# Copy_of_SCH_Placa_presentation.net
KiCad netlist of a schematic drawn in Altium Designer
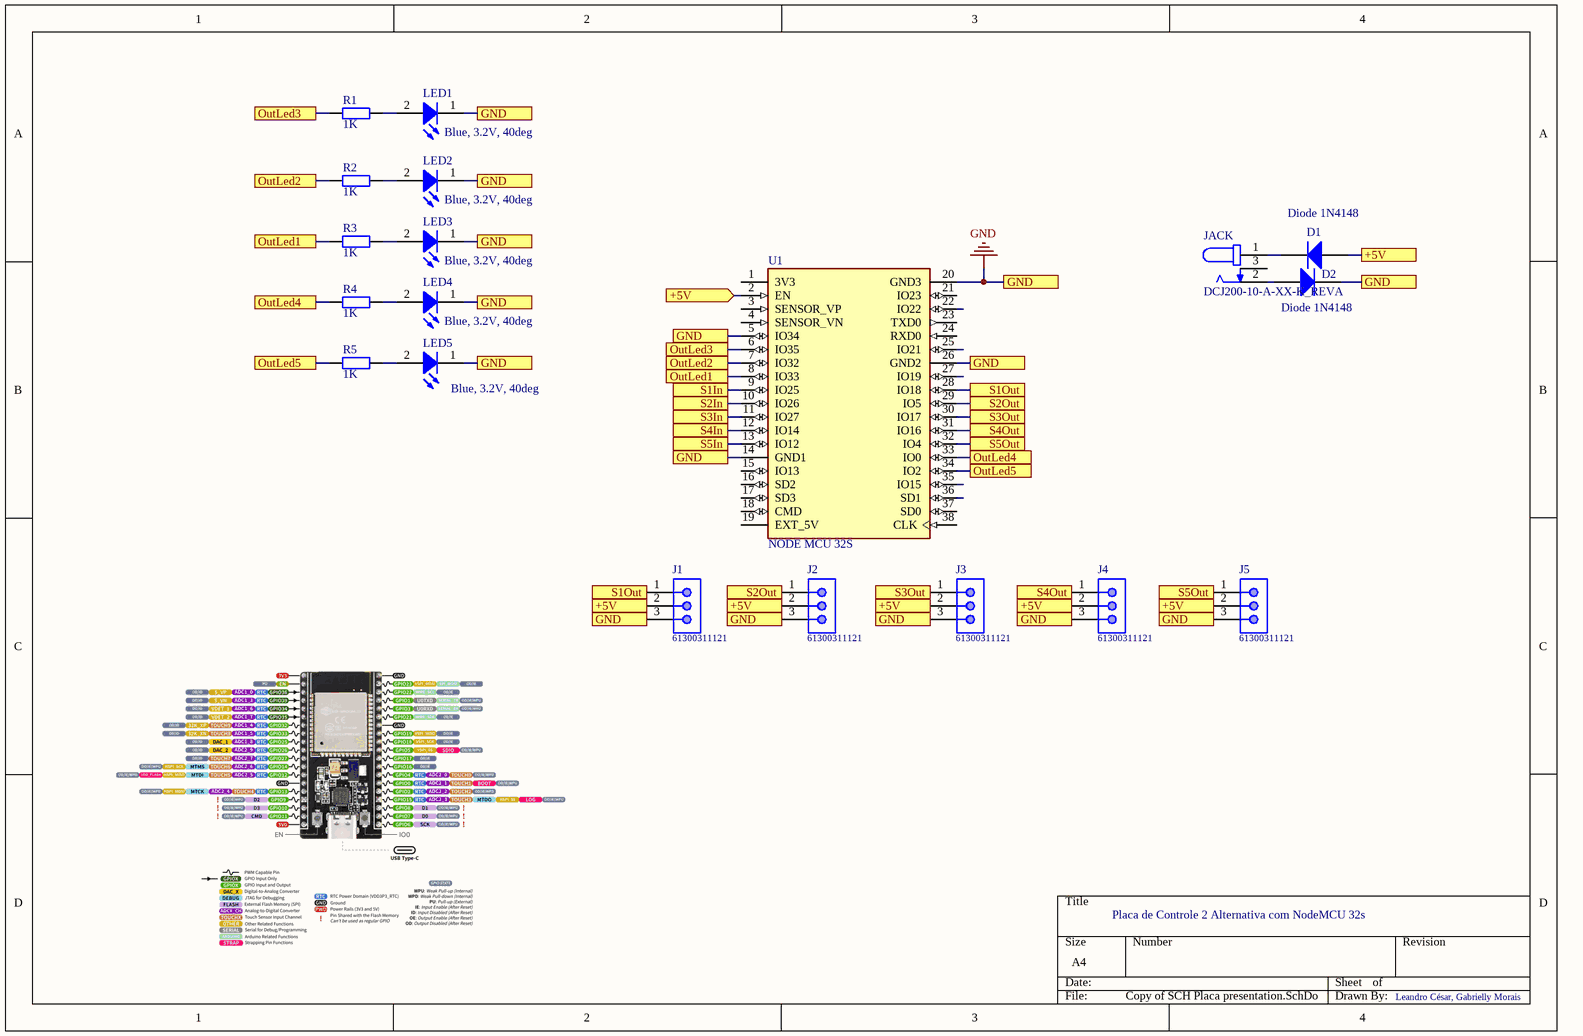
[diagram p0: Copy of SCH Placa presentation.SchDoc]

(export (version "E")
  (design (tool "Eeschema 10.0.6"))
  (components
    (comp (ref "D1")
      (value "Diode 1N4148")
      (footprint "DO-35")
      (description "High Conductance Fast Diode")
      (fields (field (name "PUBLISHER") "Altium Limited"))
      (libsource (lib "Biblioteca_Ex_Machina_v1.6.0") (part "Diode 1N4148"))
    )
    (comp (ref "D2")
      (value "Diode 1N4148")
      (footprint "DO-35")
      (description "High Conductance Fast Diode")
      (fields (field (name "PUBLISHER") "Altium Limited"))
      (libsource (lib "Biblioteca_Ex_Machina_v1.6.0") (part "Diode 1N4148"))
    )
    (comp (ref "J1")
      (value "61300311121")
      (footprint "61300311121")
      (description "WR-PHD Pin Header, THT, pitch 2.54mm, Single Row, Vertical, 3pin")
      (fields (field (name "PUBLISHER") "Wurth Elektronik"))
      (libsource (lib "Biblioteca_Ex_Machina_v1.6.0") (part "61300311121"))
    )
    (comp (ref "J2")
      (value "61300311121")
      (footprint "61300311121")
      (description "WR-PHD Pin Header, THT, pitch 2.54mm, Single Row, Vertical, 3pin")
      (fields (field (name "PUBLISHER") "Wurth Elektronik"))
      (libsource (lib "Biblioteca_Ex_Machina_v1.6.0") (part "61300311121"))
    )
    (comp (ref "J3")
      (value "61300311121")
      (footprint "61300311121")
      (description "WR-PHD Pin Header, THT, pitch 2.54mm, Single Row, Vertical, 3pin")
      (fields (field (name "PUBLISHER") "Wurth Elektronik"))
      (libsource (lib "Biblioteca_Ex_Machina_v1.6.0") (part "61300311121"))
    )
    (comp (ref "J4")
      (value "61300311121")
      (footprint "61300311121")
      (description "WR-PHD Pin Header, THT, pitch 2.54mm, Single Row, Vertical, 3pin")
      (fields (field (name "PUBLISHER") "Wurth Elektronik"))
      (libsource (lib "Biblioteca_Ex_Machina_v1.6.0") (part "61300311121"))
    )
    (comp (ref "J5")
      (value "61300311121")
      (footprint "61300311121")
      (description "WR-PHD Pin Header, THT, pitch 2.54mm, Single Row, Vertical, 3pin")
      (fields (field (name "PUBLISHER") "Wurth Elektronik"))
      (libsource (lib "Biblioteca_Ex_Machina_v1.6.0") (part "61300311121"))
    )
    (comp (ref "JACK")
      (value "DCJ200-10-A-XX-K_REVA")
      (footprint "GCT_DCJ200-10-A-XX-K_REVA")
      (description "Power Barrel Connector Jack 2.05mm ID (0.081), 5.50mm OD (0.217) Through Hole, Right Angle")
      (fields (field (name "MF") "Global Connector Technology") (field (name "MP") "DCJ200-10-A-K1-K"))
      (libsource (lib "DCJ200-10-A-XX-K_REVA (2)") (part "DCJ200-10-A-XX-K_REVA"))
    )
    (comp (ref "LED1")
      (value "Blue, 3.2V, 40deg")
      (footprint "LED RED 3MM")
      (description "LED WL-TMRC THT Mono-color Round")
      (fields (field (name "PART NUMBER") "151051BS04000") (field (name "PUBLISHER") "Wurth Elektronik"))
      (libsource (lib "Biblioteca_Ex_Machina_v1.6.0") (part "LED"))
    )
    (comp (ref "LED2")
      (value "Blue, 3.2V, 40deg")
      (footprint "LED RED 3MM")
      (description "LED WL-TMRC THT Mono-color Round")
      (fields (field (name "PART NUMBER") "151051BS04000") (field (name "PUBLISHER") "Wurth Elektronik"))
      (libsource (lib "Biblioteca_Ex_Machina_v1.6.0") (part "LED"))
    )
    (comp (ref "LED3")
      (value "Blue, 3.2V, 40deg")
      (footprint "LED RED 3MM")
      (description "LED WL-TMRC THT Mono-color Round")
      (fields (field (name "PART NUMBER") "151051BS04000") (field (name "PUBLISHER") "Wurth Elektronik"))
      (libsource (lib "Biblioteca_Ex_Machina_v1.6.0") (part "LED"))
    )
    (comp (ref "LED4")
      (value "Blue, 3.2V, 40deg")
      (footprint "LED RED 3MM")
      (description "LED WL-TMRC THT Mono-color Round")
      (fields (field (name "PART NUMBER") "151051BS04000") (field (name "PUBLISHER") "Wurth Elektronik"))
      (libsource (lib "Biblioteca_Ex_Machina_v1.6.0") (part "LED"))
    )
    (comp (ref "LED5")
      (value "Blue, 3.2V, 40deg")
      (footprint "LED RED 3MM")
      (description "LED WL-TMRC THT Mono-color Round")
      (fields (field (name "PART NUMBER") "151051BS04000") (field (name "PUBLISHER") "Wurth Elektronik"))
      (libsource (lib "Biblioteca_Ex_Machina_v1.6.0") (part "LED"))
    )
    (comp (ref "R1")
      (value "1K")
      (footprint "RES AXIAL-0.4")
      (description "Resistor")
      (fields (field (name "Comment") "Res") (field (name "PUBLISHER") "Altium Limited"))
      (libsource (lib "Biblioteca_Ex_Machina_v1.6.0") (part "Res"))
    )
    (comp (ref "R2")
      (value "1K")
      (footprint "RES AXIAL-0.4")
      (description "Resistor")
      (fields (field (name "Comment") "Res") (field (name "PUBLISHER") "Altium Limited"))
      (libsource (lib "Biblioteca_Ex_Machina_v1.6.0") (part "Res"))
    )
    (comp (ref "R3")
      (value "1K")
      (footprint "RES AXIAL-0.4")
      (description "Resistor")
      (fields (field (name "Comment") "Res") (field (name "PUBLISHER") "Altium Limited"))
      (libsource (lib "Biblioteca_Ex_Machina_v1.6.0") (part "Res"))
    )
    (comp (ref "R4")
      (value "1K")
      (footprint "RES AXIAL-0.4")
      (description "Resistor")
      (fields (field (name "Comment") "Res") (field (name "PUBLISHER") "Altium Limited"))
      (libsource (lib "Biblioteca_Ex_Machina_v1.6.0") (part "Res"))
    )
    (comp (ref "R5")
      (value "1K")
      (footprint "RES AXIAL-0.4")
      (description "Resistor")
      (fields (field (name "Comment") "Res") (field (name "PUBLISHER") "Altium Limited"))
      (libsource (lib "Biblioteca_Ex_Machina_v1.6.0") (part "Res"))
    )
    (comp (ref "U1")
      (value "NODE MCU 32S")
      (footprint "BOARD")
      (fields (field (name "MP") "ESP32-DEVKITC-32D") (field (name "MF") "Espressif Systems"))
      (libsource (lib "Biblioteca_Ex_Machina_v1.6.0") (part "NODE MCU 32S"))
    )
  )
  (nets
    (net (code "1") (name "/+5V") (class "Default")
      (node (ref "D1") (pin "1") (pinfunction "A_1") (pintype "passive"))
      (node (ref "J1") (pin "2") (pinfunction "2_2") (pintype "passive"))
      (node (ref "J2") (pin "2") (pinfunction "2_2") (pintype "passive"))
      (node (ref "J3") (pin "2") (pinfunction "2_2") (pintype "passive"))
      (node (ref "J4") (pin "2") (pinfunction "2_2") (pintype "passive"))
      (node (ref "J5") (pin "2") (pinfunction "2_2") (pintype "passive"))
      (node (ref "U1") (pin "2") (pinfunction "EN_2") (pintype "input"))
    )
    (net (code "2") (name "/OutLed1") (class "Default")
      (node (ref "R3") (pin "1") (pinfunction "1_1") (pintype "passive"))
      (node (ref "U1") (pin "8") (pinfunction "IO33_8") (pintype "bidirectional"))
    )
    (net (code "3") (name "/OutLed2") (class "Default")
      (node (ref "R2") (pin "1") (pinfunction "1_1") (pintype "passive"))
      (node (ref "U1") (pin "7") (pinfunction "IO32_7") (pintype "bidirectional"))
    )
    (net (code "4") (name "/OutLed3") (class "Default")
      (node (ref "R1") (pin "1") (pinfunction "1_1") (pintype "passive"))
      (node (ref "U1") (pin "6") (pinfunction "IO35_6") (pintype "bidirectional"))
    )
    (net (code "5") (name "/OutLed4") (class "Default")
      (node (ref "R4") (pin "1") (pinfunction "1_1") (pintype "passive"))
      (node (ref "U1") (pin "33") (pinfunction "IO0_33") (pintype "bidirectional"))
    )
    (net (code "6") (name "/OutLed5") (class "Default")
      (node (ref "R5") (pin "1") (pinfunction "1_1") (pintype "passive"))
      (node (ref "U1") (pin "34") (pinfunction "IO2_34") (pintype "bidirectional"))
    )
    (net (code "7") (name "/S1In") (class "Default")
      (node (ref "U1") (pin "9") (pinfunction "IO25_9") (pintype "bidirectional"))
    )
    (net (code "8") (name "/S1Out") (class "Default")
      (node (ref "J1") (pin "1") (pinfunction "1_1") (pintype "passive"))
      (node (ref "U1") (pin "28") (pinfunction "IO18_28") (pintype "bidirectional"))
    )
    (net (code "9") (name "/S2In") (class "Default")
      (node (ref "U1") (pin "10") (pinfunction "IO26_10") (pintype "bidirectional"))
    )
    (net (code "10") (name "/S2Out") (class "Default")
      (node (ref "J2") (pin "1") (pinfunction "1_1") (pintype "passive"))
      (node (ref "U1") (pin "29") (pinfunction "IO5_29") (pintype "bidirectional"))
    )
    (net (code "11") (name "/S3In") (class "Default")
      (node (ref "U1") (pin "11") (pinfunction "IO27_11") (pintype "bidirectional"))
    )
    (net (code "12") (name "/S3Out") (class "Default")
      (node (ref "J3") (pin "1") (pinfunction "1_1") (pintype "passive"))
      (node (ref "U1") (pin "30") (pinfunction "IO17_30") (pintype "bidirectional"))
    )
    (net (code "13") (name "/S4In") (class "Default")
      (node (ref "U1") (pin "12") (pinfunction "IO14_12") (pintype "bidirectional"))
    )
    (net (code "14") (name "/S4Out") (class "Default")
      (node (ref "J4") (pin "1") (pinfunction "1_1") (pintype "passive"))
      (node (ref "U1") (pin "31") (pinfunction "IO16_31") (pintype "bidirectional"))
    )
    (net (code "15") (name "/S5In") (class "Default")
      (node (ref "U1") (pin "13") (pinfunction "IO12_13") (pintype "bidirectional"))
    )
    (net (code "16") (name "/S5Out") (class "Default")
      (node (ref "J5") (pin "1") (pinfunction "1_1") (pintype "passive"))
      (node (ref "U1") (pin "32") (pinfunction "IO4_32") (pintype "bidirectional"))
    )
    (net (code "17") (name "GND") (class "Default")
      (node (ref "D2") (pin "2") (pinfunction "K_2") (pintype "passive"))
      (node (ref "J1") (pin "3") (pinfunction "3_3") (pintype "passive"))
      (node (ref "J2") (pin "3") (pinfunction "3_3") (pintype "passive"))
      (node (ref "J3") (pin "3") (pinfunction "3_3") (pintype "passive"))
      (node (ref "J4") (pin "3") (pinfunction "3_3") (pintype "passive"))
      (node (ref "J5") (pin "3") (pinfunction "3_3") (pintype "passive"))
      (node (ref "LED1") (pin "1") (pinfunction "K_1") (pintype "passive"))
      (node (ref "LED2") (pin "1") (pinfunction "K_1") (pintype "passive"))
      (node (ref "LED3") (pin "1") (pinfunction "K_1") (pintype "passive"))
      (node (ref "LED4") (pin "1") (pinfunction "K_1") (pintype "passive"))
      (node (ref "LED5") (pin "1") (pinfunction "K_1") (pintype "passive"))
      (node (ref "U1") (pin "14") (pinfunction "GND1_14") (pintype "power_in"))
      (node (ref "U1") (pin "20") (pinfunction "GND3_20") (pintype "power_in"))
      (node (ref "U1") (pin "26") (pinfunction "GND2_26") (pintype "power_in"))
      (node (ref "U1") (pin "5") (pinfunction "IO34_5") (pintype "bidirectional"))
    )
    (net (code "18") (name "Net-(D1-K)") (class "Default")
      (node (ref "D1") (pin "2") (pinfunction "K_2") (pintype "passive"))
      (node (ref "JACK") (pin "1") (pinfunction "1_1") (pintype "passive"))
    )
    (net (code "19") (name "Net-(D2-A)") (class "Default")
      (node (ref "D2") (pin "1") (pinfunction "A_1") (pintype "passive"))
      (node (ref "JACK") (pin "2") (pinfunction "2_2") (pintype "passive"))
    )
    (net (code "20") (name "Net-(LED1-A)") (class "Default")
      (node (ref "LED1") (pin "2") (pinfunction "A_2") (pintype "passive"))
      (node (ref "R1") (pin "2") (pinfunction "2_2") (pintype "passive"))
    )
    (net (code "21") (name "Net-(LED2-A)") (class "Default")
      (node (ref "LED2") (pin "2") (pinfunction "A_2") (pintype "passive"))
      (node (ref "R2") (pin "2") (pinfunction "2_2") (pintype "passive"))
    )
    (net (code "22") (name "Net-(LED3-A)") (class "Default")
      (node (ref "LED3") (pin "2") (pinfunction "A_2") (pintype "passive"))
      (node (ref "R3") (pin "2") (pinfunction "2_2") (pintype "passive"))
    )
    (net (code "23") (name "Net-(LED4-A)") (class "Default")
      (node (ref "LED4") (pin "2") (pinfunction "A_2") (pintype "passive"))
      (node (ref "R4") (pin "2") (pinfunction "2_2") (pintype "passive"))
    )
    (net (code "24") (name "Net-(LED5-A)") (class "Default")
      (node (ref "LED5") (pin "2") (pinfunction "A_2") (pintype "passive"))
      (node (ref "R5") (pin "2") (pinfunction "2_2") (pintype "passive"))
    )
    (net (code "25") (name "unconnected-(JACK-Pad3)") (class "Default")
      (node (ref "JACK") (pin "3") (pinfunction "3_3") (pintype "passive"))
    )
    (net (code "26") (name "unconnected-(U1-3V3-Pad1)") (class "Default")
      (node (ref "U1") (pin "1") (pinfunction "3V3_1") (pintype "power_in"))
    )
    (net (code "27") (name "unconnected-(U1-CLK-Pad38)") (class "Default")
      (node (ref "U1") (pin "38") (pinfunction "CLK_38") (pintype "input"))
    )
    (net (code "28") (name "unconnected-(U1-CMD-Pad18)") (class "Default")
      (node (ref "U1") (pin "18") (pinfunction "CMD_18") (pintype "bidirectional"))
    )
    (net (code "29") (name "unconnected-(U1-EXT_5V-Pad19)") (class "Default")
      (node (ref "U1") (pin "19") (pinfunction "EXT_5V_19") (pintype "power_in"))
    )
    (net (code "30") (name "unconnected-(U1-IO13-Pad15)") (class "Default")
      (node (ref "U1") (pin "15") (pinfunction "IO13_15") (pintype "bidirectional"))
    )
    (net (code "31") (name "unconnected-(U1-IO15-Pad35)") (class "Default")
      (node (ref "U1") (pin "35") (pinfunction "IO15_35") (pintype "bidirectional"))
    )
    (net (code "32") (name "unconnected-(U1-IO19-Pad27)") (class "Default")
      (node (ref "U1") (pin "27") (pinfunction "IO19_27") (pintype "bidirectional"))
    )
    (net (code "33") (name "unconnected-(U1-IO21-Pad25)") (class "Default")
      (node (ref "U1") (pin "25") (pinfunction "IO21_25") (pintype "bidirectional"))
    )
    (net (code "34") (name "unconnected-(U1-IO22-Pad22)") (class "Default")
      (node (ref "U1") (pin "22") (pinfunction "IO22_22") (pintype "bidirectional"))
    )
    (net (code "35") (name "unconnected-(U1-IO23-Pad21)") (class "Default")
      (node (ref "U1") (pin "21") (pinfunction "IO23_21") (pintype "bidirectional"))
    )
    (net (code "36") (name "unconnected-(U1-RXD0-Pad24)") (class "Default")
      (node (ref "U1") (pin "24") (pinfunction "RXD0_24") (pintype "input"))
    )
    (net (code "37") (name "unconnected-(U1-SD0-Pad37)") (class "Default")
      (node (ref "U1") (pin "37") (pinfunction "SD0_37") (pintype "bidirectional"))
    )
    (net (code "38") (name "unconnected-(U1-SD1-Pad36)") (class "Default")
      (node (ref "U1") (pin "36") (pinfunction "SD1_36") (pintype "bidirectional"))
    )
    (net (code "39") (name "unconnected-(U1-SD2-Pad16)") (class "Default")
      (node (ref "U1") (pin "16") (pinfunction "SD2_16") (pintype "bidirectional"))
    )
    (net (code "40") (name "unconnected-(U1-SD3-Pad17)") (class "Default")
      (node (ref "U1") (pin "17") (pinfunction "SD3_17") (pintype "bidirectional"))
    )
    (net (code "41") (name "unconnected-(U1-SENSOR_VN-Pad4)") (class "Default")
      (node (ref "U1") (pin "4") (pinfunction "SENSOR_VN_4") (pintype "input"))
    )
    (net (code "42") (name "unconnected-(U1-SENSOR_VP-Pad3)") (class "Default")
      (node (ref "U1") (pin "3") (pinfunction "SENSOR_VP_3") (pintype "input"))
    )
    (net (code "43") (name "unconnected-(U1-TXD0-Pad23)") (class "Default")
      (node (ref "U1") (pin "23") (pinfunction "TXD0_23") (pintype "output"))
    )
  )
)
